# Motor_Control.net
KiCad netlist of a schematic drawn in Altium Designer
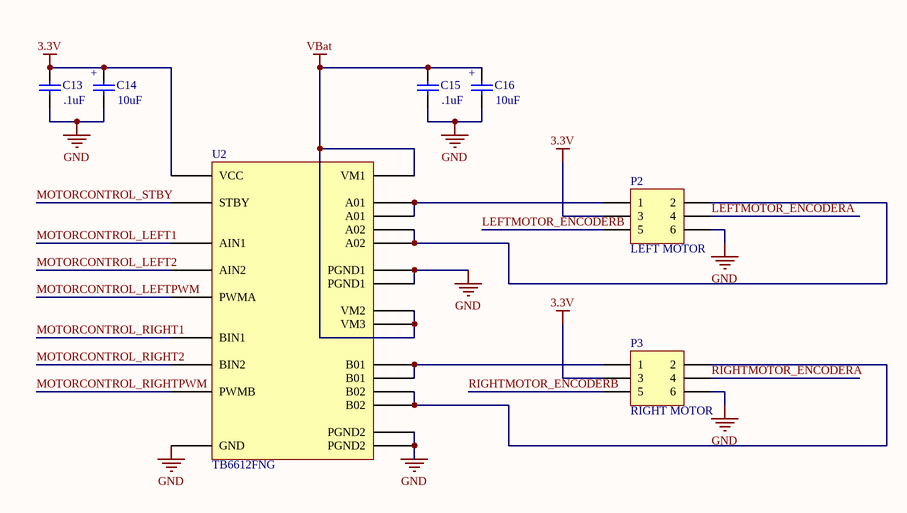
[diagram p0: Motor Control.SchDoc]

(export (version "E")
  (design (tool "Eeschema 10.0.6"))
  (components
    (comp (ref "C13")
      (value ".1uF")
      (footprint "1608[0603]")
      (description "Capacitor (Semiconductor SIM Model)")
      (fields (field (name "Comment") "Cap Semi") (field (name "PUBLISHER") "Altium Limited"))
      (libsource (lib "Miscellaneous Devices") (part "Cap Semi"))
    )
    (comp (ref "C14")
      (value "10uF")
      (footprint "1608[0603]")
      (description "Capacitor (Semiconductor SIM Model)")
      (fields (field (name "Comment") "Cap Semi") (field (name "PUBLISHER") "Altium Limited"))
      (libsource (lib "Miscellaneous Devices") (part "Cap Semi"))
    )
    (comp (ref "C15")
      (value ".1uF")
      (footprint "1608[0603]")
      (description "Capacitor (Semiconductor SIM Model)")
      (fields (field (name "Comment") "Cap Semi") (field (name "PUBLISHER") "Altium Limited"))
      (libsource (lib "Miscellaneous Devices") (part "Cap Semi"))
    )
    (comp (ref "C16")
      (value "10uF")
      (footprint "C1210")
      (description "Capacitor (Semiconductor SIM Model)")
      (fields (field (name "Comment") "Cap Semi") (field (name "PUBLISHER") "Altium Limited"))
      (libsource (lib "Miscellaneous Devices") (part "Cap Semi"))
    )
    (comp (ref "P2")
      (value "LEFT MOTOR")
      (footprint "HDR2X3")
      (description "Header, 3-Pin, Dual row")
      (fields (field (name "PUBLISHER") "Altium Limited"))
      (libsource (lib "Miscellaneous Connectors") (part "Header 3X2"))
    )
    (comp (ref "P3")
      (value "RIGHT MOTOR")
      (footprint "HDR2X3")
      (description "Header, 3-Pin, Dual row")
      (fields (field (name "PUBLISHER") "Altium Limited"))
      (libsource (lib "Miscellaneous Connectors") (part "Header 3X2"))
    )
    (comp (ref "U2")
      (value "TB6612FNG")
      (footprint "SSOP24-P-300-0.65A")
      (fields
        (field (name "VENDOR PART NO.") "TB6612FNG(OC8EL)CT-ND")
        (field (name "MANUFACTURER") "Toshiba")
      )
      (libsource (lib "Devices") (part "TB6612FNG"))
    )
  )
  (nets
    (net (code "1") (name "/LEFTMOTOR_ENCODERA") (class "Default")
      (node (ref "P2") (pin "4") (pinfunction "4_4") (pintype "passive"))
    )
    (net (code "2") (name "/LEFTMOTOR_ENCODERB") (class "Default")
      (node (ref "P2") (pin "5") (pinfunction "5_5") (pintype "passive"))
    )
    (net (code "3") (name "/MOTORCONTROL_LEFT1") (class "Default")
      (node (ref "U2") (pin "21") (pinfunction "AIN1_21") (pintype "passive"))
    )
    (net (code "4") (name "/MOTORCONTROL_LEFT2") (class "Default")
      (node (ref "U2") (pin "22") (pinfunction "AIN2_22") (pintype "passive"))
    )
    (net (code "5") (name "/MOTORCONTROL_LEFTPWM") (class "Default")
      (node (ref "U2") (pin "23") (pinfunction "PWMA_23") (pintype "passive"))
    )
    (net (code "6") (name "/MOTORCONTROL_RIGHT1") (class "Default")
      (node (ref "U2") (pin "17") (pinfunction "BIN1_17") (pintype "passive"))
    )
    (net (code "7") (name "/MOTORCONTROL_RIGHT2") (class "Default")
      (node (ref "U2") (pin "16") (pinfunction "BIN2_16") (pintype "passive"))
    )
    (net (code "8") (name "/MOTORCONTROL_RIGHTPWM") (class "Default")
      (node (ref "U2") (pin "15") (pinfunction "PWMB_15") (pintype "passive"))
    )
    (net (code "9") (name "/MOTORCONTROL_STBY") (class "Default")
      (node (ref "U2") (pin "19") (pinfunction "STBY_19") (pintype "passive"))
    )
    (net (code "10") (name "/RIGHTMOTOR_ENCODERA") (class "Default")
      (node (ref "P3") (pin "4") (pinfunction "4_4") (pintype "passive"))
    )
    (net (code "11") (name "/RIGHTMOTOR_ENCODERB") (class "Default")
      (node (ref "P3") (pin "5") (pinfunction "5_5") (pintype "passive"))
    )
    (net (code "12") (name "3.3V") (class "Default")
      (node (ref "C13") (pin "2") (pinfunction "2_2") (pintype "passive"))
      (node (ref "C14") (pin "2") (pinfunction "2_2") (pintype "passive"))
      (node (ref "P2") (pin "3") (pinfunction "3_3") (pintype "passive"))
      (node (ref "P3") (pin "3") (pinfunction "3_3") (pintype "passive"))
      (node (ref "U2") (pin "20") (pinfunction "VCC_20") (pintype "passive"))
    )
    (net (code "13") (name "GND") (class "Default")
      (node (ref "C13") (pin "1") (pinfunction "1_1") (pintype "passive"))
      (node (ref "C14") (pin "1") (pinfunction "1_1") (pintype "passive"))
      (node (ref "C15") (pin "1") (pinfunction "1_1") (pintype "passive"))
      (node (ref "C16") (pin "1") (pinfunction "1_1") (pintype "passive"))
      (node (ref "P2") (pin "6") (pinfunction "6_6") (pintype "passive"))
      (node (ref "P3") (pin "6") (pinfunction "6_6") (pintype "passive"))
      (node (ref "U2") (pin "10") (pinfunction "PGND2_10") (pintype "passive"))
      (node (ref "U2") (pin "18") (pinfunction "GND_18") (pintype "passive"))
      (node (ref "U2") (pin "3") (pinfunction "PGND1_3") (pintype "passive"))
      (node (ref "U2") (pin "4") (pinfunction "PGND1_4") (pintype "passive"))
      (node (ref "U2") (pin "9") (pinfunction "PGND2_9") (pintype "passive"))
    )
    (net (code "14") (name "Net-(P2-Pad1)") (class "Default")
      (node (ref "P2") (pin "1") (pinfunction "1_1") (pintype "passive"))
      (node (ref "U2") (pin "1") (pinfunction "A01_1") (pintype "passive"))
      (node (ref "U2") (pin "2") (pinfunction "A01_2") (pintype "passive"))
    )
    (net (code "15") (name "Net-(P2-Pad2)") (class "Default")
      (node (ref "P2") (pin "2") (pinfunction "2_2") (pintype "passive"))
      (node (ref "U2") (pin "5") (pinfunction "A02_5") (pintype "passive"))
      (node (ref "U2") (pin "6") (pinfunction "A02_6") (pintype "passive"))
    )
    (net (code "16") (name "Net-(P3-Pad1)") (class "Default")
      (node (ref "P3") (pin "1") (pinfunction "1_1") (pintype "passive"))
      (node (ref "U2") (pin "11") (pinfunction "B01_11") (pintype "passive"))
      (node (ref "U2") (pin "12") (pinfunction "B01_12") (pintype "passive"))
    )
    (net (code "17") (name "Net-(P3-Pad2)") (class "Default")
      (node (ref "P3") (pin "2") (pinfunction "2_2") (pintype "passive"))
      (node (ref "U2") (pin "7") (pinfunction "B02_7") (pintype "passive"))
      (node (ref "U2") (pin "8") (pinfunction "B02_8") (pintype "passive"))
    )
    (net (code "18") (name "VBat") (class "Default")
      (node (ref "C15") (pin "2") (pinfunction "2_2") (pintype "passive"))
      (node (ref "C16") (pin "2") (pinfunction "2_2") (pintype "passive"))
      (node (ref "U2") (pin "13") (pinfunction "VM2_13") (pintype "passive"))
      (node (ref "U2") (pin "14") (pinfunction "VM3_14") (pintype "passive"))
      (node (ref "U2") (pin "24") (pinfunction "VM1_24") (pintype "passive"))
    )
  )
)
